# bmp581.net
KiCad netlist of a schematic drawn in EAGLE
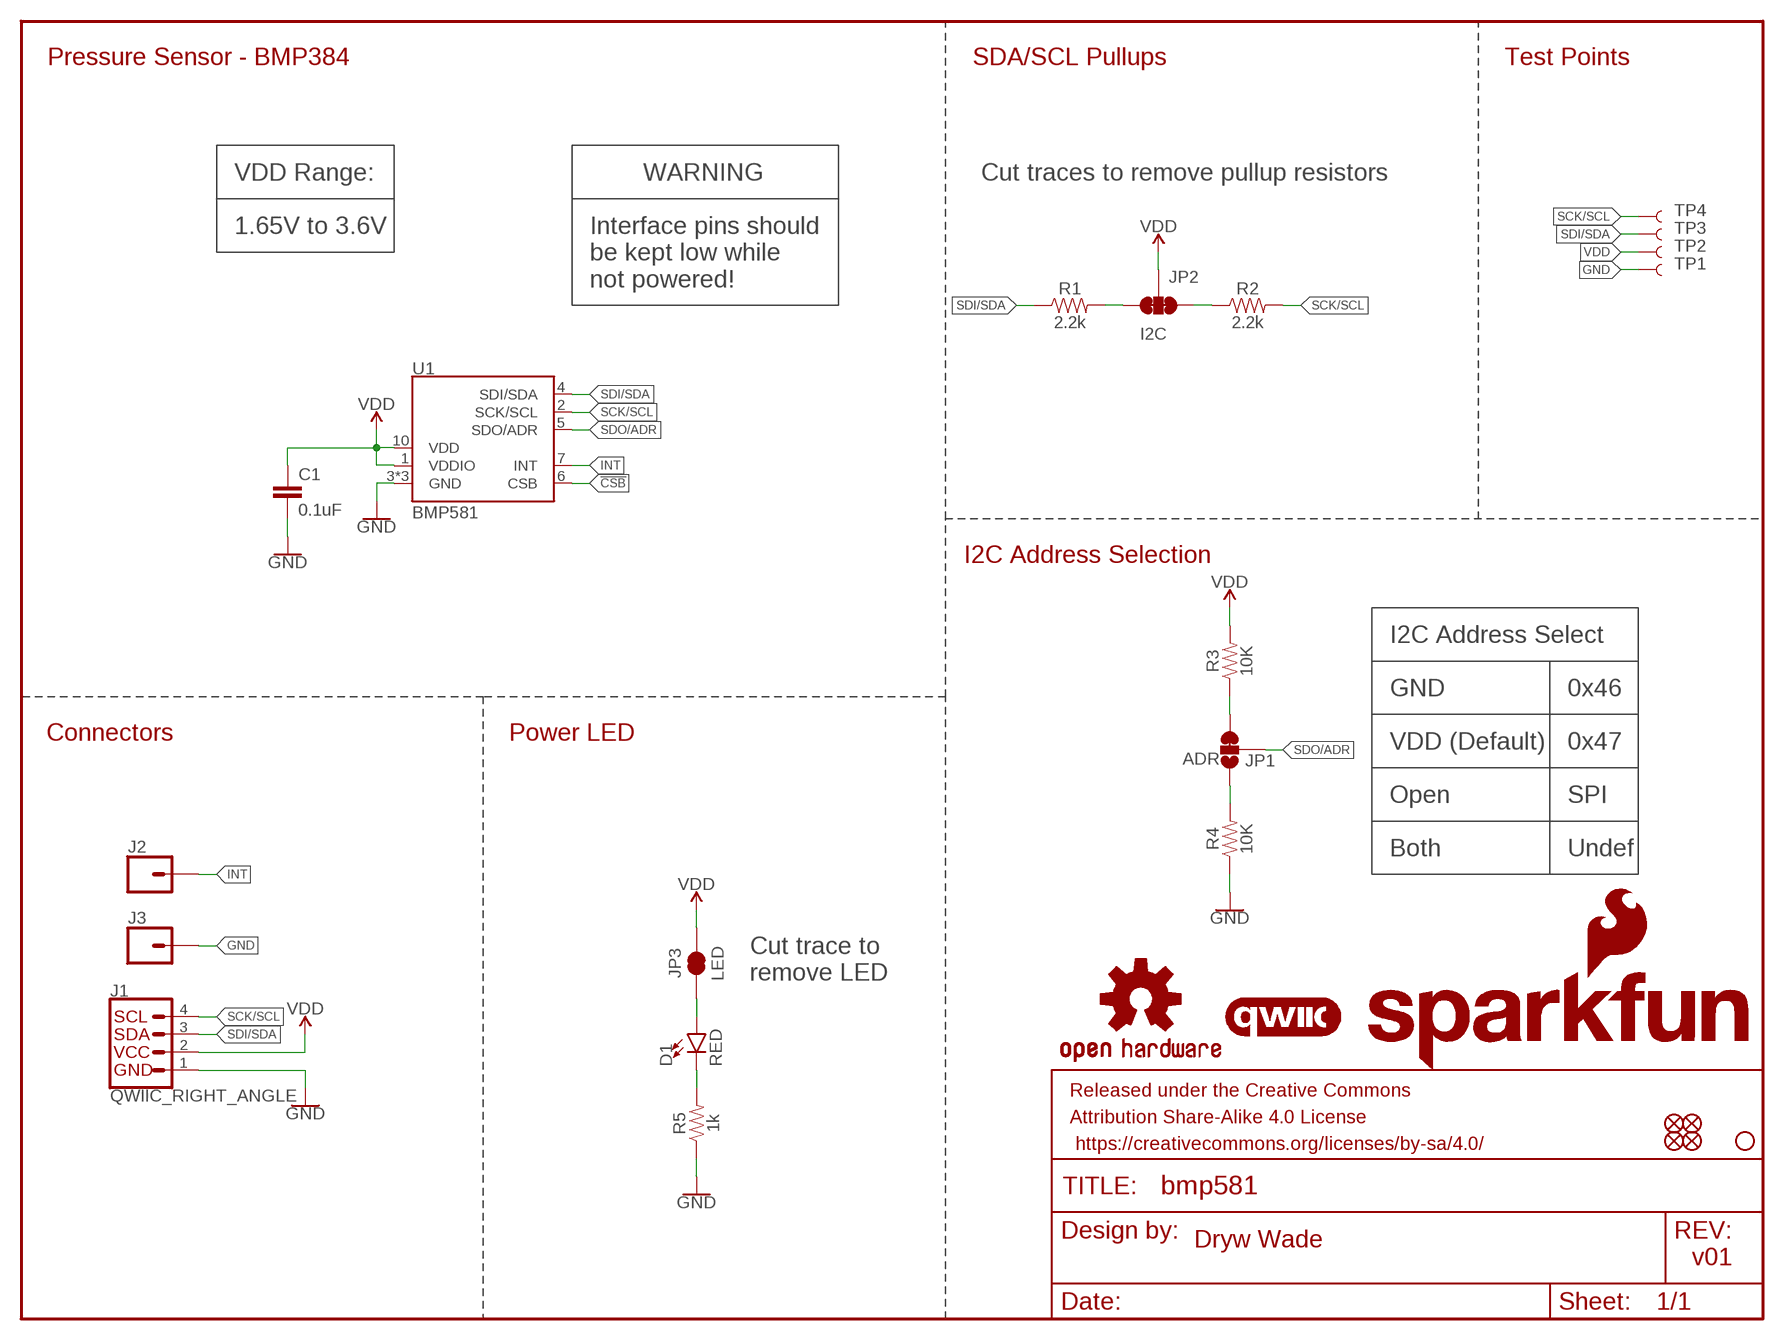
[diagram p0: schematic, sheet 1]

(export (version "E")
  (design (tool "Eeschema 10.0.6"))
  (components
    (comp (ref "C1")
      (value "0.1uF")
      (footprint "eagle-import:0402-TIGHT")
      (libsource (lib "eagle-import") (part "0.1UF-0402T-6.3V-10%-X7R"))
    )
    (comp (ref "D1")
      (value "RED")
      (footprint "eagle-import:LED-0402")
      (libsource (lib "eagle-import") (part "LED-RED_0402"))
    )
    (comp (ref "FD1")
      (value "FIDUCIALUFIDUCIAL")
      (footprint "eagle-import:FIDUCIAL-MICRO")
      (libsource (lib "eagle-import") (part "FIDUCIALUFIDUCIAL"))
    )
    (comp (ref "FD2")
      (value "FIDUCIALUFIDUCIAL")
      (footprint "eagle-import:FIDUCIAL-MICRO")
      (libsource (lib "eagle-import") (part "FIDUCIALUFIDUCIAL"))
    )
    (comp (ref "FD3")
      (value "FIDUCIALUFIDUCIAL")
      (footprint "eagle-import:FIDUCIAL-MICRO")
      (libsource (lib "eagle-import") (part "FIDUCIALUFIDUCIAL"))
    )
    (comp (ref "FD4")
      (value "FIDUCIALUFIDUCIAL")
      (footprint "eagle-import:FIDUCIAL-MICRO")
      (libsource (lib "eagle-import") (part "FIDUCIALUFIDUCIAL"))
    )
    (comp (ref "FRAME1")
      (value "FRAME-LETTER")
      (footprint "eagle-import:CREATIVE_COMMONS")
      (libsource (lib "eagle-import") (part "FRAME-LETTER"))
    )
    (comp (ref "H1")
      (value "STAND-OFF")
      (footprint "eagle-import:STAND-OFF")
      (libsource (lib "eagle-import") (part "STAND-OFF"))
    )
    (comp (ref "J1")
      (value "QWIIC_RIGHT_ANGLE")
      (footprint "eagle-import:JST04_1MM_RA")
      (libsource (lib "eagle-import") (part "QWIIC_CONNECTORJS-1MM"))
    )
    (comp (ref "J2")
      (value "CONN_01_1MM")
      (footprint "eagle-import:1X01_1MM_NO_SILK")
      (libsource (lib "eagle-import") (part "CONN_01_1MM"))
    )
    (comp (ref "J3")
      (value "CONN_01_1MM")
      (footprint "eagle-import:1X01_1MM_NO_SILK")
      (libsource (lib "eagle-import") (part "CONN_01_1MM"))
    )
    (comp (ref "JP1")
      (value "ADR")
      (footprint "eagle-import:SMT-JUMPER_3_1-NC_TRACE_SILK")
      (libsource (lib "eagle-import") (part "JUMPER-SMT_3_1-NC_TRACE_SILK"))
    )
    (comp (ref "JP2")
      (value "I2C")
      (footprint "eagle-import:SMT-JUMPER_3_2-NC_TRACE_SILK")
      (libsource (lib "eagle-import") (part "JUMPER-SMT_3_2-NC_TRACE_SILK"))
    )
    (comp (ref "JP3")
      (value "LED")
      (footprint "eagle-import:SMT-JUMPER_2_NC_TRACE_SILK")
      (libsource (lib "eagle-import") (part "JUMPER-SMT_2_NC_TRACE_SILK"))
    )
    (comp (ref "LOGO1")
      (value "OSHW-LOGOMINI")
      (footprint "eagle-import:OSHW-LOGO-MINI")
      (libsource (lib "eagle-import") (part "OSHW-LOGOMINI"))
    )
    (comp (ref "LOGO2")
      (value "SFE_LOGO_FLAME.1_INCH")
      (footprint "eagle-import:SFE_LOGO_FLAME_.1")
      (libsource (lib "eagle-import") (part "SFE_LOGO_FLAME.1_INCH"))
    )
    (comp (ref "LOGO3")
      (value "QWIIC_LOGO_3MM")
      (footprint "eagle-import:QWIIC_3MM")
      (libsource (lib "eagle-import") (part "QWIIC_LOGO_3MM"))
    )
    (comp (ref "LOGO4")
      (value "SFE_LOGO_NAMEBLANK")
      (footprint "eagle-import:BLANK")
      (libsource (lib "eagle-import") (part "SFE_LOGO_NAMEBLANK"))
    )
    (comp (ref "R1")
      (value "2.2k")
      (footprint "eagle-import:0402-TIGHT")
      (libsource (lib "eagle-import") (part "2.2KOHM-0402T-1/16W-1%"))
    )
    (comp (ref "R2")
      (value "2.2k")
      (footprint "eagle-import:0402-TIGHT")
      (libsource (lib "eagle-import") (part "2.2KOHM-0402T-1/16W-1%"))
    )
    (comp (ref "R3")
      (value "10K")
      (footprint "eagle-import:0402-TIGHT")
      (libsource (lib "eagle-import") (part "10KOHM-0402-1/10W-0.1%"))
    )
    (comp (ref "R4")
      (value "10K")
      (footprint "eagle-import:0402-TIGHT")
      (libsource (lib "eagle-import") (part "10KOHM-0402-1/10W-0.1%"))
    )
    (comp (ref "R5")
      (value "1k")
      (footprint "eagle-import:0402-TIGHT")
      (libsource (lib "eagle-import") (part "1KOHM-0402T-1/16W-1%"))
    )
    (comp (ref "TP1")
      (value "TEST-POINT3")
      (footprint "eagle-import:PAD.03X.03")
      (libsource (lib "eagle-import") (part "TEST-POINT3"))
    )
    (comp (ref "TP2")
      (value "TEST-POINT3")
      (footprint "eagle-import:PAD.03X.03")
      (libsource (lib "eagle-import") (part "TEST-POINT3"))
    )
    (comp (ref "TP3")
      (value "TEST-POINT3")
      (footprint "eagle-import:PAD.03X.03")
      (libsource (lib "eagle-import") (part "TEST-POINT3"))
    )
    (comp (ref "TP4")
      (value "TEST-POINT3")
      (footprint "eagle-import:PAD.03X.03")
      (libsource (lib "eagle-import") (part "TEST-POINT3"))
    )
    (comp (ref "U1")
      (value "BMP581")
      (footprint "eagle-import:BMP581")
      (libsource (lib "eagle-import") (part "BMP581"))
    )
  )
  (nets
    (net (code "1") (name "/~{CSB}") (class "Default")
      (node (ref "U1") (pin "6") (pinfunction "CSB_6") (pintype "input"))
    )
    (net (code "2") (name "GND") (class "Default")
      (node (ref "C1") (pin "2") (pinfunction "2_2") (pintype "passive"))
      (node (ref "J1") (pin "1") (pinfunction "1_1") (pintype "power_in"))
      (node (ref "J3") (pin "1") (pinfunction "1_1") (pintype "passive"))
      (node (ref "R4") (pin "1") (pinfunction "1_1") (pintype "passive"))
      (node (ref "R5") (pin "1") (pinfunction "1_1") (pintype "passive"))
      (node (ref "TP1") (pin "1") (pinfunction "1_1") (pintype "bidirectional"))
      (node (ref "U1") (pin "3") (pinfunction "GND_3") (pintype "power_in"))
      (node (ref "U1") (pin "8") (pinfunction "GND_8") (pintype "power_in"))
      (node (ref "U1") (pin "9") (pinfunction "GND_9") (pintype "power_in"))
    )
    (net (code "3") (name "INT") (class "Default")
      (node (ref "J2") (pin "1") (pinfunction "1_1") (pintype "passive"))
      (node (ref "U1") (pin "7") (pinfunction "INT_7") (pintype "output"))
    )
    (net (code "4") (name "Net-(D1-PadA)") (class "Default")
      (node (ref "D1") (pin "A") (pinfunction "A_A") (pintype "passive"))
      (node (ref "JP3") (pin "1") (pinfunction "1_1") (pintype "passive"))
    )
    (net (code "5") (name "Net-(D1-PadC)") (class "Default")
      (node (ref "D1") (pin "C") (pinfunction "C_C") (pintype "passive"))
      (node (ref "R5") (pin "2") (pinfunction "2_2") (pintype "passive"))
    )
    (net (code "6") (name "Net-(JP1-Pad1)") (class "Default")
      (node (ref "JP1") (pin "1") (pinfunction "1_1") (pintype "passive"))
      (node (ref "R4") (pin "2") (pinfunction "2_2") (pintype "passive"))
    )
    (net (code "7") (name "Net-(JP1-Pad3)") (class "Default")
      (node (ref "JP1") (pin "3") (pinfunction "3_3") (pintype "passive"))
      (node (ref "R3") (pin "1") (pinfunction "1_1") (pintype "passive"))
    )
    (net (code "8") (name "Net-(JP2-Pad1)") (class "Default")
      (node (ref "JP2") (pin "1") (pinfunction "1_1") (pintype "passive"))
      (node (ref "R2") (pin "1") (pinfunction "1_1") (pintype "passive"))
    )
    (net (code "9") (name "Net-(JP2-Pad3)") (class "Default")
      (node (ref "JP2") (pin "3") (pinfunction "3_3") (pintype "passive"))
      (node (ref "R1") (pin "2") (pinfunction "2_2") (pintype "passive"))
    )
    (net (code "10") (name "SCK{slash}SCL") (class "Default")
      (node (ref "J1") (pin "4") (pinfunction "4_4") (pintype "passive"))
      (node (ref "R2") (pin "2") (pinfunction "2_2") (pintype "passive"))
      (node (ref "TP4") (pin "1") (pinfunction "1_1") (pintype "bidirectional"))
      (node (ref "U1") (pin "2") (pinfunction "SCK/SCL_2") (pintype "bidirectional"))
    )
    (net (code "11") (name "SDI{slash}SDA") (class "Default")
      (node (ref "J1") (pin "3") (pinfunction "3_3") (pintype "passive"))
      (node (ref "R1") (pin "1") (pinfunction "1_1") (pintype "passive"))
      (node (ref "TP3") (pin "1") (pinfunction "1_1") (pintype "bidirectional"))
      (node (ref "U1") (pin "4") (pinfunction "SDI/SDA_4") (pintype "bidirectional"))
    )
    (net (code "12") (name "SDO{slash}ADR") (class "Default")
      (node (ref "JP1") (pin "2") (pinfunction "2_2") (pintype "passive"))
      (node (ref "U1") (pin "5") (pinfunction "SDO/ADR_5") (pintype "bidirectional"))
    )
    (net (code "13") (name "VDD") (class "Default")
      (node (ref "C1") (pin "1") (pinfunction "1_1") (pintype "passive"))
      (node (ref "J1") (pin "2") (pinfunction "2_2") (pintype "power_in"))
      (node (ref "JP2") (pin "2") (pinfunction "2_2") (pintype "passive"))
      (node (ref "JP3") (pin "2") (pinfunction "2_2") (pintype "passive"))
      (node (ref "R3") (pin "2") (pinfunction "2_2") (pintype "passive"))
      (node (ref "TP2") (pin "1") (pinfunction "1_1") (pintype "bidirectional"))
      (node (ref "U1") (pin "1") (pinfunction "VDDIO_1") (pintype "power_in"))
      (node (ref "U1") (pin "10") (pinfunction "VDD_10") (pintype "power_in"))
    )
  )
)
